# BPPower_Management.net
KiCad netlist of a schematic drawn in Altium Designer
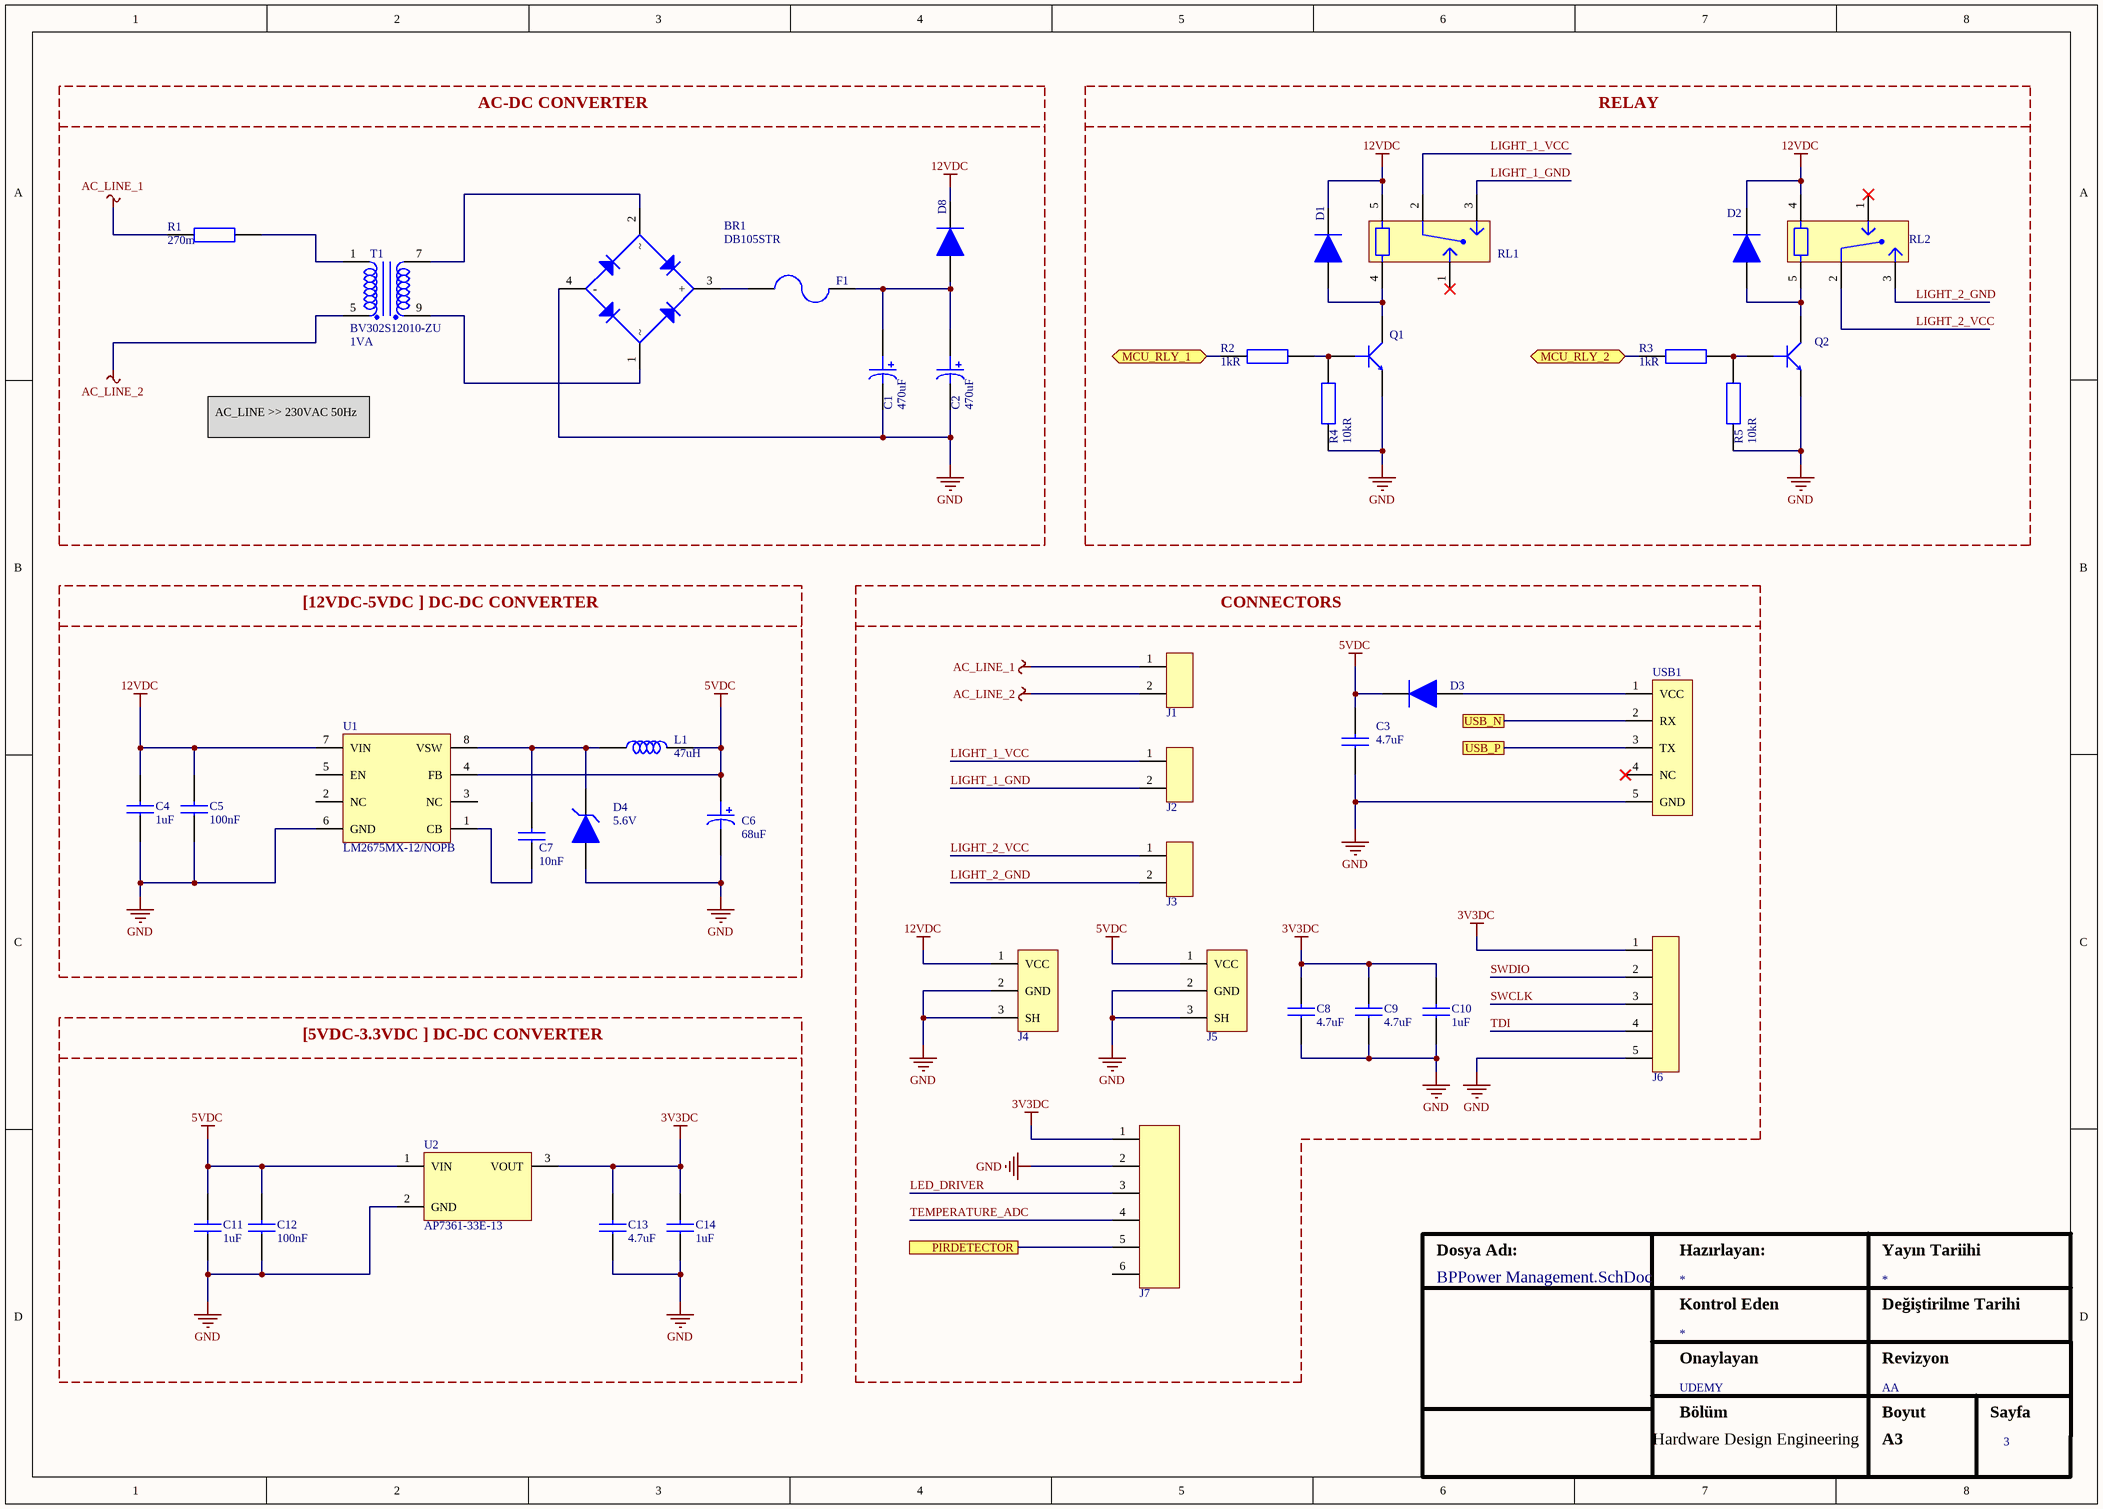
[diagram p0: BPPower Management.SchDoc]

(export (version "E")
  (design (tool "Eeschema 10.0.6"))
  (components
    (comp (ref "BR1")
      (value "DB105STR")
      (footprint "DB105STR")
      (description "Bridge Diode AC-DC")
      (fields (field (name "MANUFACTURER") "Sangdest Microelectronics") (field (name "DESIGNED BY") "BERK"))
      (libsource (lib "UDEMY_Library") (part "DB105STR"))
    )
    (comp (ref "C1")
      (value "ESH477M050AH4AA")
      (footprint "CAP_RADIAL_D10_P5")
      (description "CAP ALU ELEC 470uF 50V RADIAL")
      (fields
        (field (name "MANUFACTURER") "KEMET")
        (field (name "TOLERANCE") "20%")
        (field (name "CAPACITANCE") "470uF")
        (field (name "DESIGNED BY") "BERK")
      )
      (libsource (lib "UDEMY_Library") (part "CAP ALU ELEC 470uF 50V"))
    )
    (comp (ref "C2")
      (value "ESH477M050AH4AA")
      (footprint "CAP_RADIAL_D10_P5")
      (description "CAP ALU ELEC 470uF 50V RADIAL")
      (fields
        (field (name "MANUFACTURER") "KEMET")
        (field (name "TOLERANCE") "20%")
        (field (name "CAPACITANCE") "470uF")
        (field (name "DESIGNED BY") "BERK")
      )
      (libsource (lib "UDEMY_Library") (part "CAP ALU ELEC 470uF 50V"))
    )
    (comp (ref "C3")
      (value "CL21A475KAQNNNE")
      (footprint "CAP_0805")
      (description "CAP CER 4.7uF %10 0805")
      (fields
        (field (name "MANUFACTURER") "Samsung")
        (field (name "TOLERANCE") "10%")
        (field (name "CAPACITANCE") "4.7uF")
        (field (name "DESIGNED BY") "BERK")
      )
      (libsource (lib "UDEMY_Library") (part "CAP CER 4.7uF 0805"))
    )
    (comp (ref "C4")
      (value "CL21B105KBFNNNE")
      (footprint "CAP_0805")
      (description "CAP CER 1uF %10 0805")
      (fields
        (field (name "MANUFACTURER") "Samsung")
        (field (name "TOLERANCE") "10%")
        (field (name "CAPACITANCE") "1uF")
        (field (name "DESIGNED BY") "BERK")
      )
      (libsource (lib "UDEMY_Library") (part "CAP CER 1uF 0805"))
    )
    (comp (ref "C5")
      (value "CL21B104KBCNNNC")
      (footprint "CAP_0805")
      (description "CAP CER 100nF %10 0805")
      (fields
        (field (name "MANUFACTURER") "Samsung")
        (field (name "TOLERANCE") "10%")
        (field (name "CAPACITANCE") "100nF")
        (field (name "DESIGNED BY") "BERK")
      )
      (libsource (lib "UDEMY_Library") (part "CAP CER 100nF 0805"))
    )
    (comp (ref "C6")
      (value "EEV686M035A9HAA")
      (footprint "CAP_EEVseries")
      (description "Cap Aluminum Lytic 68uF 35V 20% (6.3 X 7.7mm) SMD 280mA 2000h 105C T/R")
      (fields
        (field (name "MANUFACTURER") "KEMET")
        (field (name "TOLERANCE") "20%")
        (field (name "CAPACITANCE") "68uF")
      )
      (libsource (lib "UDEMY_Library") (part "CAP ALU 68uF"))
    )
    (comp (ref "C7")
      (value "0603B103K160CT")
      (footprint "CAP_0603")
      (description "CAP CER 10nF %10 0603")
      (fields
        (field (name "MANUFACTURER") "Walsin Technologies")
        (field (name "TOLERANCE") "10%")
        (field (name "CAPACITANCE") "10nF")
        (field (name "DESIGNED BY") "BERK")
      )
      (libsource (lib "UDEMY_Library") (part "CAP CER 10nF 0603"))
    )
    (comp (ref "C8")
      (value "CL21A475KAQNNNE")
      (footprint "CAP_0805")
      (description "CAP CER 4.7uF %10 0805")
      (fields
        (field (name "MANUFACTURER") "Samsung")
        (field (name "TOLERANCE") "10%")
        (field (name "CAPACITANCE") "4.7uF")
        (field (name "DESIGNED BY") "BERK")
      )
      (libsource (lib "UDEMY_Library") (part "CAP CER 4.7uF 0805"))
    )
    (comp (ref "C9")
      (value "CL21A475KAQNNNE")
      (footprint "CAP_0805")
      (description "CAP CER 4.7uF %10 0805")
      (fields
        (field (name "MANUFACTURER") "Samsung")
        (field (name "TOLERANCE") "10%")
        (field (name "CAPACITANCE") "4.7uF")
        (field (name "DESIGNED BY") "BERK")
      )
      (libsource (lib "UDEMY_Library") (part "CAP CER 4.7uF 0805"))
    )
    (comp (ref "C10")
      (value "CL21B105KBFNNNE")
      (footprint "CAP_0805")
      (description "CAP CER 1uF %10 0805")
      (fields
        (field (name "MANUFACTURER") "Samsung")
        (field (name "TOLERANCE") "10%")
        (field (name "CAPACITANCE") "1uF")
        (field (name "DESIGNED BY") "BERK")
      )
      (libsource (lib "UDEMY_Library") (part "CAP CER 1uF 0805"))
    )
    (comp (ref "C11")
      (value "CL21B105KBFNNNE")
      (footprint "CAP_0805")
      (description "CAP CER 1uF %10 0805")
      (fields
        (field (name "MANUFACTURER") "Samsung")
        (field (name "TOLERANCE") "10%")
        (field (name "CAPACITANCE") "1uF")
        (field (name "DESIGNED BY") "BERK")
      )
      (libsource (lib "UDEMY_Library") (part "CAP CER 1uF 0805"))
    )
    (comp (ref "C12")
      (value "C0603C104K5RACTU")
      (footprint "CAP_0603")
      (description "CAP CER 100nF %10 0603 SMD")
      (fields
        (field (name "MANUFACTURER") "KEMET")
        (field (name "TOLERANCE") "10%")
        (field (name "CAPACITANCE") "100nF")
        (field (name "DESIGNED BY") "BERK")
      )
      (libsource (lib "UDEMY_Library") (part "CAP CER 100nF 0603"))
    )
    (comp (ref "C13")
      (value "CL21A475KAQNNNE")
      (footprint "CAP_0805")
      (description "CAP CER 4.7uF %10 0805")
      (fields
        (field (name "MANUFACTURER") "Samsung")
        (field (name "TOLERANCE") "10%")
        (field (name "CAPACITANCE") "4.7uF")
        (field (name "DESIGNED BY") "BERK")
      )
      (libsource (lib "UDEMY_Library") (part "CAP CER 4.7uF 0805"))
    )
    (comp (ref "C14")
      (value "CL21B105KBFNNNE")
      (footprint "CAP_0805")
      (description "CAP CER 1uF %10 0805")
      (fields
        (field (name "MANUFACTURER") "Samsung")
        (field (name "TOLERANCE") "10%")
        (field (name "CAPACITANCE") "1uF")
        (field (name "DESIGNED BY") "BERK")
      )
      (libsource (lib "UDEMY_Library") (part "CAP CER 1uF 0805"))
    )
    (comp (ref "D1")
      (value "1N4148WS")
      (footprint "SOD323F")
      (description "Diode, Single, 75 V, 150 mA, 1 V, 4 ns")
      (fields
        (field (name "MANUFACTURER") "ON Semiconductor / Fairchild")
        (field (name "DESIGNED BY") "BERK")
      )
      (libsource (lib "UDEMY_Library") (part "1N4148WS"))
    )
    (comp (ref "D2")
      (value "1N4148WS")
      (footprint "SOD323F")
      (description "Diode, Single, 75 V, 150 mA, 1 V, 4 ns")
      (fields
        (field (name "MANUFACTURER") "ON Semiconductor / Fairchild")
        (field (name "DESIGNED BY") "BERK")
      )
      (libsource (lib "UDEMY_Library") (part "1N4148WS"))
    )
    (comp (ref "D3")
      (value "1N4148WS")
      (footprint "SOD323F")
      (description "Diode, Single, 75 V, 150 mA, 1 V, 4 ns")
      (fields
        (field (name "MANUFACTURER") "ON Semiconductor / Fairchild")
        (field (name "DESIGNED BY") "BERK")
      )
      (libsource (lib "UDEMY_Library") (part "1N4148WS"))
    )
    (comp (ref "D4")
      (value "1SMB5919BT3G")
      (footprint "SMB")
      (description "Diode Zener Single 5.6V 5% 3W 2-Pin SMB T/R")
      (fields
        (field (name "MANUFACTURER") "ON Semiconductor")
        (field (name "TOLERANCE") "5%")
        (field (name "WORKING VOLTAGE") "5.6V")
        (field (name "DESIGNED BY") "BERK")
      )
      (libsource (lib "UDEMY_Library") (part "1SMB5919BT3G"))
    )
    (comp (ref "D8")
      (value "1N4148WS")
      (footprint "SOD323F")
      (description "Diode, Single, 75 V, 150 mA, 1 V, 4 ns")
      (fields
        (field (name "MANUFACTURER") "ON Semiconductor / Fairchild")
        (field (name "DESIGNED BY") "BERK")
      )
      (libsource (lib "UDEMY_Library") (part "1N4148WS"))
    )
    (comp (ref "F1")
      (value "3413.0216.22")
      (footprint "BPSchematic:3413.0216.22")
      (description "FUSE BRD MNT 1A 32VAC 63VDC 1206")
      (fields (field (name "MANUFACTURER") "Schurter") (field (name "DESIGNED BY") "BERK"))
      (libsource (lib "UDEMY_Library") (part "FUSE 3413.0216.22"))
    )
    (comp (ref "J1")
      (value "TBP01R1-508-02BE")
      (footprint "BPSchematic:TBP01R1-508")
      (description "Conn Shrouded Header HDR 2 POS 5.08mm Solder RA Side Entry Thru-Hole Bag")
      (fields (field (name "MANUFACTURER") "CUI") (field (name "DESIGNED BY") "BERK"))
      (libsource (lib "UDEMY_Library") (part "TBP01R1-508-02BE"))
    )
    (comp (ref "J2")
      (value "TBP01R1-508-02BE")
      (footprint "BPSchematic:TBP01R1-508")
      (description "Conn Shrouded Header HDR 2 POS 5.08mm Solder RA Side Entry Thru-Hole Bag")
      (fields (field (name "MANUFACTURER") "CUI") (field (name "DESIGNED BY") "BERK"))
      (libsource (lib "UDEMY_Library") (part "TBP01R1-508-02BE"))
    )
    (comp (ref "J3")
      (value "TBP01R1-508-02BE")
      (footprint "BPSchematic:TBP01R1-508")
      (description "Conn Shrouded Header HDR 2 POS 5.08mm Solder RA Side Entry Thru-Hole Bag")
      (fields (field (name "MANUFACTURER") "CUI") (field (name "DESIGNED BY") "BERK"))
      (libsource (lib "UDEMY_Library") (part "TBP01R1-508-02BE"))
    )
    (comp (ref "J4")
      (value "PJ-037AH-SMT-TR")
      (footprint "JACK")
      (description "DC Power Connectors Power Jacks")
      (fields (field (name "MANUFACTURER") "CUI") (field (name "DESIGNED BY") "BERK"))
      (libsource (lib "UDEMY_Library") (part "PJ-037AH-SMT-TR"))
    )
    (comp (ref "J5")
      (value "PJ-037AH-SMT-TR")
      (footprint "JACK")
      (description "DC Power Connectors Power Jacks")
      (fields (field (name "MANUFACTURER") "CUI") (field (name "DESIGNED BY") "BERK"))
      (libsource (lib "UDEMY_Library") (part "PJ-037AH-SMT-TR"))
    )
    (comp (ref "J6")
      (value "SMH-105-02-L-S")
      (footprint "PINHEADER1X5_RA")
      (description ".100 C.L. HORIZONTAL SMT SOCKET")
      (fields (field (name "MANUFACTURER") "Samtec") (field (name "DESIGNED BY") "BERK"))
      (libsource (lib "UDEMY_Library") (part "SMH-105-02-L-S"))
    )
    (comp (ref "J7")
      (value "64800611622")
      (footprint "BPSchematic:64800611622")
      (description "1.50mm 6PIN Connector")
      (fields (field (name "MANUFACTURER") "Wurth Electronics"))
      (libsource (lib "UDEMY_Library") (part "64800611622_conn_6pin"))
    )
    (comp (ref "L1")
      (value "78438335470")
      (footprint "IND_1212")
      (description "FIXED IND 47UH 390MA 2.3 OHM SMD")
      (fields
        (field (name "MANUFACTURER") "Wurth Electronics")
        (field (name "TOLERANCE") "30%")
        (field (name "INDUCTANCE") "47uH")
        (field (name "DESIGNED BY") "BERK")
      )
      (libsource (lib "UDEMY_Library") (part "IND 47uH"))
    )
    (comp (ref "Q1")
      (value "MMBT3904-7-F")
      (footprint "SOT-23F")
      (description "Transistor General Purpose BJT NPN 40 Volt 0.2A Automotive 3-Pin SOT-23")
      (fields (field (name "MANUFACTURER") "Diodes Zetex") (field (name "DESIGNED BY") "BERK"))
      (libsource (lib "UDEMY_Library") (part "MMBT3904-7-F"))
    )
    (comp (ref "Q2")
      (value "MMBT3904-7-F")
      (footprint "SOT-23F")
      (description "Transistor General Purpose BJT NPN 40 Volt 0.2A Automotive 3-Pin SOT-23")
      (fields (field (name "MANUFACTURER") "Diodes Zetex") (field (name "DESIGNED BY") "BERK"))
      (libsource (lib "UDEMY_Library") (part "MMBT3904-7-F"))
    )
    (comp (ref "R1")
      (value "5WD27")
      (footprint "RES_AXIAL_W")
      (description "Resistor 5 Watt Cermet Wirewound Flameproof .27 Ohm 5% Axial Lead")
      (fields
        (field (name "MANUFACTURER") "NTE Electronics")
        (field (name "TOLERANCE") "5%")
        (field (name "RESISTANCE") "270m")
        (field (name "DESIGNED BY") "BERK")
      )
      (libsource (lib "UDEMY_Library") (part "5WD27"))
    )
    (comp (ref "R2")
      (value "RC0603FR-0710KL")
      (footprint "RES_0603")
      (description "RES 1K %1 OHM 0603 SMD")
      (fields
        (field (name "MANUFACTURER") "Yageo")
        (field (name "MANUFACTURER PART NUMBER") "RC0603JR-071KL")
        (field (name "RESISTANCE") "1kR")
        (field (name "DESIGNED BY") "BERK")
      )
      (libsource (lib "UDEMY_Library") (part "RES 1K OHM 0603"))
    )
    (comp (ref "R3")
      (value "RC0603FR-0710KL")
      (footprint "RES_0603")
      (description "RES 1K %1 OHM 0603 SMD")
      (fields
        (field (name "MANUFACTURER") "Yageo")
        (field (name "MANUFACTURER PART NUMBER") "RC0603JR-071KL")
        (field (name "RESISTANCE") "1kR")
        (field (name "DESIGNED BY") "BERK")
      )
      (libsource (lib "UDEMY_Library") (part "RES 1K OHM 0603"))
    )
    (comp (ref "R4")
      (value "RC0603FR-0710KL")
      (footprint "RES_0603")
      (description "RES 10K %1 OHM 0603 SMD")
      (fields
        (field (name "MANUFACTURER") "Yageo")
        (field (name "TOLERANCE") "1%")
        (field (name "RESISTANCE") "10kR")
        (field (name "DESIGNED BY") "BERK")
      )
      (libsource (lib "UDEMY_Library") (part "RES 10K OHM 0603"))
    )
    (comp (ref "R5")
      (value "RC0603FR-0710KL")
      (footprint "RES_0603")
      (description "RES 10K %1 OHM 0603 SMD")
      (fields
        (field (name "MANUFACTURER") "Yageo")
        (field (name "TOLERANCE") "1%")
        (field (name "RESISTANCE") "10kR")
        (field (name "DESIGNED BY") "BERK")
      )
      (libsource (lib "UDEMY_Library") (part "RES 10K OHM 0603"))
    )
    (comp (ref "RL1")
      (value "ALQ112")
      (footprint "ALQ112")
      (description "General Purpose Relay SPDT (1 Form C) 12VDC Coil Through Hole")
      (fields (field (name "MANUFACTURER") "Panasonic") (field (name "DESIGNED BY") "BERK"))
      (libsource (lib "") (part "ALQ112_1"))
    )
    (comp (ref "RL2")
      (value "ALQ112")
      (footprint "ALQ112")
      (description "General Purpose Relay SPDT (1 Form C) 12VDC Coil Through Hole")
      (fields (field (name "MANUFACTURER") "Panasonic") (field (name "DESIGNED BY") "BERK"))
      (libsource (lib "UDEMY_Library") (part "ALQ112"))
    )
    (comp (ref "T1")
      (value "BV302S12010-ZU")
      (footprint "BV302S")
      (description "230-12 Transformer 1VA")
      (fields
        (field (name "MANUFACTURER") "Zettler Magnetics")
        (field (name "RATED POWER") "1VA")
        (field (name "DESIGNED BY") "BERK")
      )
      (libsource (lib "UDEMY_Library") (part "BV302S12010-ZU"))
    )
    (comp (ref "U1")
      (value "LM2675MX-12/NOPB")
      (footprint "SOIC8")
      (description "Switching Voltage Regulators Pwr Cnvtr Hi Eff 1A SD Vtg Reg")
      (fields (field (name "MANUFACTURER") "TI National Semiconductor") (field (name "DESIGNED BY") "BERK"))
      (libsource (lib "UDEMY_Library") (part "LM2675MX-12/NOPB"))
    )
    (comp (ref "U2")
      (value "AP7361-33E-13")
      (footprint "SOT223")
      (description "LDO Regulator Pos 3.3V 1A 4-Pin(3+Tab) SOT-223 T/R")
      (fields (field (name "MANUFACTURER") "Diodes") (field (name "DESIGNED BY") "BERK"))
      (libsource (lib "UDEMY_Library") (part "AP7361-33E-13"))
    )
    (comp (ref "USB1")
      (value "10118192-0001LF")
      (footprint "MICRO_B_USB")
      (description "CONN RCPT USB2.0 MICRO B SMD R/A")
      (fields (field (name "MANUFACTURER") "Amphenol FCI") (field (name "DESIGNED BY") "BERK"))
      (libsource (lib "UDEMY_Library") (part "Micro B USB Connector"))
    )
  )
  (nets
    (net (code "1") (name "/LED_DRIVER") (class "Default") (node (ref "J7") (pin "3") (pintype "power_in")))
    (net (code "2") (name "/LIGHT_1_GND") (class "Default")
      (node (ref "J2") (pin "2") (pinfunction "2_2") (pintype "power_in"))
      (node (ref "RL1") (pin "3") (pinfunction "3_3") (pintype "passive"))
    )
    (net (code "3") (name "/LIGHT_1_VCC") (class "Default")
      (node (ref "J2") (pin "1") (pinfunction "1_1") (pintype "power_in"))
      (node (ref "RL1") (pin "2") (pinfunction "2_2") (pintype "passive"))
    )
    (net (code "4") (name "/LIGHT_2_GND") (class "Default")
      (node (ref "J3") (pin "2") (pinfunction "2_2") (pintype "power_in"))
      (node (ref "RL2") (pin "3") (pinfunction "3_3") (pintype "passive"))
    )
    (net (code "5") (name "/LIGHT_2_VCC") (class "Default")
      (node (ref "J3") (pin "1") (pinfunction "1_1") (pintype "power_in"))
      (node (ref "RL2") (pin "2") (pinfunction "2_2") (pintype "passive"))
    )
    (net (code "6") (name "/MCU_RLY_1") (class "Default")
      (node (ref "R2") (pin "1") (pinfunction "1_1") (pintype "passive"))
    )
    (net (code "7") (name "/MCU_RLY_2") (class "Default")
      (node (ref "R3") (pin "1") (pinfunction "1_1") (pintype "passive"))
    )
    (net (code "8") (name "/PIRDETECTOR") (class "Default") (node (ref "J7") (pin "5") (pintype "power_in")))
    (net (code "9") (name "/SWCLK") (class "Default")
      (node (ref "J6") (pin "3") (pinfunction "3_3") (pintype "power_in"))
    )
    (net (code "10") (name "/SWDIO") (class "Default")
      (node (ref "J6") (pin "2") (pinfunction "2_2") (pintype "power_in"))
    )
    (net (code "11") (name "/TDI") (class "Default")
      (node (ref "J6") (pin "4") (pinfunction "4_4") (pintype "power_in"))
    )
    (net (code "12") (name "/TEMPERATURE_ADC") (class "Default")
      (node (ref "J7") (pin "4") (pintype "power_in"))
    )
    (net (code "13") (name "/USB_N") (class "Default")
      (node (ref "USB1") (pin "2") (pinfunction "RX_2") (pintype "power_in"))
    )
    (net (code "14") (name "/USB_P") (class "Default")
      (node (ref "USB1") (pin "3") (pinfunction "TX_3") (pintype "power_in"))
    )
    (net (code "15") (name "3V3DC") (class "Default")
      (node (ref "C10") (pin "2") (pinfunction "2_2") (pintype "passive"))
      (node (ref "C13") (pin "2") (pinfunction "2_2") (pintype "passive"))
      (node (ref "C14") (pin "2") (pinfunction "2_2") (pintype "passive"))
      (node (ref "C8") (pin "2") (pinfunction "2_2") (pintype "passive"))
      (node (ref "C9") (pin "2") (pinfunction "2_2") (pintype "passive"))
      (node (ref "J6") (pin "1") (pinfunction "1_1") (pintype "power_in"))
      (node (ref "J7") (pin "1") (pintype "power_in"))
      (node (ref "U2") (pin "3") (pinfunction "VOUT_3") (pintype "passive"))
    )
    (net (code "16") (name "5VDC") (class "Default")
      (node (ref "C11") (pin "2") (pinfunction "2_2") (pintype "passive"))
      (node (ref "C12") (pin "2") (pinfunction "2_2") (pintype "passive"))
      (node (ref "C3") (pin "2") (pinfunction "2_2") (pintype "passive"))
      (node (ref "C6") (pin "1") (pinfunction "1_1") (pintype "passive"))
      (node (ref "D3") (pin "1") (pinfunction "1_1") (pintype "power_in"))
      (node (ref "J5") (pin "1") (pinfunction "VCC_1") (pintype "power_in"))
      (node (ref "L1") (pin "2") (pinfunction "2_2") (pintype "passive"))
      (node (ref "U1") (pin "4") (pinfunction "FB_4") (pintype "passive"))
      (node (ref "U2") (pin "1") (pinfunction "VIN_1") (pintype "passive"))
    )
    (net (code "17") (name "12VDC") (class "Default")
      (node (ref "C4") (pin "2") (pinfunction "2_2") (pintype "passive"))
      (node (ref "C5") (pin "2") (pinfunction "2_2") (pintype "passive"))
      (node (ref "D1") (pin "1") (pinfunction "1_1") (pintype "power_in"))
      (node (ref "D2") (pin "1") (pinfunction "1_1") (pintype "power_in"))
      (node (ref "D8") (pin "1") (pinfunction "1_1") (pintype "power_in"))
      (node (ref "J4") (pin "1") (pinfunction "VCC_1") (pintype "power_in"))
      (node (ref "RL1") (pin "5") (pinfunction "5_5") (pintype "passive"))
      (node (ref "RL2") (pin "4") (pinfunction "4_4") (pintype "passive"))
      (node (ref "U1") (pin "7") (pinfunction "VIN_7") (pintype "passive"))
    )
    (net (code "18") (name "AC_LINE_1") (class "Default")
      (node (ref "J1") (pin "1") (pinfunction "1_1") (pintype "power_in"))
      (node (ref "R1") (pin "1") (pinfunction "1_1") (pintype "passive"))
    )
    (net (code "19") (name "AC_LINE_2") (class "Default")
      (node (ref "J1") (pin "2") (pinfunction "2_2") (pintype "power_in"))
      (node (ref "T1") (pin "5") (pinfunction "5_5") (pintype "passive"))
    )
    (net (code "20") (name "GND") (class "Default")
      (node (ref "BR1") (pin "4") (pinfunction "-_4") (pintype "passive"))
      (node (ref "C1") (pin "2") (pinfunction "2_2") (pintype "passive"))
      (node (ref "C10") (pin "1") (pinfunction "1_1") (pintype "passive"))
      (node (ref "C11") (pin "1") (pinfunction "1_1") (pintype "passive"))
      (node (ref "C12") (pin "1") (pinfunction "1_1") (pintype "passive"))
      (node (ref "C13") (pin "1") (pinfunction "1_1") (pintype "passive"))
      (node (ref "C14") (pin "1") (pinfunction "1_1") (pintype "passive"))
      (node (ref "C2") (pin "2") (pinfunction "2_2") (pintype "passive"))
      (node (ref "C3") (pin "1") (pinfunction "1_1") (pintype "passive"))
      (node (ref "C4") (pin "1") (pinfunction "1_1") (pintype "passive"))
      (node (ref "C5") (pin "1") (pinfunction "1_1") (pintype "passive"))
      (node (ref "C6") (pin "2") (pinfunction "2_2") (pintype "passive"))
      (node (ref "C8") (pin "1") (pinfunction "1_1") (pintype "passive"))
      (node (ref "C9") (pin "1") (pinfunction "1_1") (pintype "passive"))
      (node (ref "D4") (pin "A") (pinfunction "A_A") (pintype "passive"))
      (node (ref "J4") (pin "2") (pinfunction "GND_2") (pintype "power_in"))
      (node (ref "J4") (pin "3") (pinfunction "SH_3") (pintype "power_in"))
      (node (ref "J5") (pin "2") (pinfunction "GND_2") (pintype "power_in"))
      (node (ref "J5") (pin "3") (pinfunction "SH_3") (pintype "power_in"))
      (node (ref "J6") (pin "5") (pinfunction "5_5") (pintype "power_in"))
      (node (ref "J7") (pin "2") (pintype "power_in"))
      (node (ref "Q1") (pin "2") (pinfunction "E_2") (pintype "power_in"))
      (node (ref "Q2") (pin "2") (pinfunction "E_2") (pintype "power_in"))
      (node (ref "R4") (pin "1") (pinfunction "1_1") (pintype "passive"))
      (node (ref "R5") (pin "1") (pinfunction "1_1") (pintype "passive"))
      (node (ref "U1") (pin "6") (pinfunction "GND_6") (pintype "passive"))
      (node (ref "U2") (pin "2") (pinfunction "GND_2") (pintype "passive"))
      (node (ref "USB1") (pin "5") (pinfunction "GND_5") (pintype "power_in"))
    )
    (net (code "21") (name "Net-(BR1-+)") (class "Default")
      (node (ref "BR1") (pin "3") (pinfunction "+_3") (pintype "passive"))
      (node (ref "F1") (pin "1") (pinfunction "1_1") (pintype "passive"))
    )
    (net (code "22") (name "Net-(BR1-~-Pad1)") (class "Default")
      (node (ref "BR1") (pin "1") (pinfunction "~_1") (pintype "passive"))
      (node (ref "T1") (pin "9") (pinfunction "9_9") (pintype "passive"))
    )
    (net (code "23") (name "Net-(BR1-~-Pad2)") (class "Default")
      (node (ref "BR1") (pin "2") (pinfunction "~_2") (pintype "passive"))
      (node (ref "T1") (pin "7") (pinfunction "7_7") (pintype "passive"))
    )
    (net (code "24") (name "Net-(C1-Pad1)") (class "Default")
      (node (ref "C1") (pin "1") (pinfunction "1_1") (pintype "passive"))
      (node (ref "C2") (pin "1") (pinfunction "1_1") (pintype "passive"))
      (node (ref "D8") (pin "2") (pinfunction "2_2") (pintype "power_in"))
      (node (ref "F1") (pin "2") (pinfunction "2_2") (pintype "passive"))
    )
    (net (code "25") (name "Net-(Q1-B)") (class "Default")
      (node (ref "Q1") (pin "1") (pinfunction "B_1") (pintype "power_in"))
      (node (ref "R2") (pin "2") (pinfunction "2_2") (pintype "passive"))
      (node (ref "R4") (pin "2") (pinfunction "2_2") (pintype "passive"))
    )
    (net (code "26") (name "Net-(Q1-C)") (class "Default")
      (node (ref "D1") (pin "2") (pinfunction "2_2") (pintype "power_in"))
      (node (ref "Q1") (pin "3") (pinfunction "C_3") (pintype "power_in"))
      (node (ref "RL1") (pin "4") (pinfunction "4_4") (pintype "passive"))
    )
    (net (code "27") (name "Net-(Q2-B)") (class "Default")
      (node (ref "Q2") (pin "1") (pinfunction "B_1") (pintype "power_in"))
      (node (ref "R3") (pin "2") (pinfunction "2_2") (pintype "passive"))
      (node (ref "R5") (pin "2") (pinfunction "2_2") (pintype "passive"))
    )
    (net (code "28") (name "Net-(Q2-C)") (class "Default")
      (node (ref "D2") (pin "2") (pinfunction "2_2") (pintype "power_in"))
      (node (ref "Q2") (pin "3") (pinfunction "C_3") (pintype "power_in"))
      (node (ref "RL2") (pin "5") (pinfunction "5_5") (pintype "passive"))
    )
    (net (code "29") (name "Net-(R1-Pad2)") (class "Default")
      (node (ref "R1") (pin "2") (pinfunction "2_2") (pintype "passive"))
      (node (ref "T1") (pin "1") (pinfunction "1_1") (pintype "passive"))
    )
    (net (code "30") (name "Net-(U1-CB)") (class "Default")
      (node (ref "C7") (pin "1") (pinfunction "1_1") (pintype "passive"))
      (node (ref "U1") (pin "1") (pinfunction "CB_1") (pintype "passive"))
    )
    (net (code "31") (name "Net-(U1-VSW)") (class "Default")
      (node (ref "C7") (pin "2") (pinfunction "2_2") (pintype "passive"))
      (node (ref "D4") (pin "C") (pinfunction "C_C") (pintype "passive"))
      (node (ref "L1") (pin "1") (pinfunction "1_1") (pintype "passive"))
      (node (ref "U1") (pin "8") (pinfunction "VSW_8") (pintype "passive"))
    )
    (net (code "32") (name "Net-(USB1-VCC)") (class "Default")
      (node (ref "D3") (pin "2") (pinfunction "2_2") (pintype "power_in"))
      (node (ref "USB1") (pin "1") (pinfunction "VCC_1") (pintype "power_in"))
    )
    (net (code "33") (name "unconnected-(J7-Pad6)") (class "Default")
      (node (ref "J7") (pin "6") (pintype "power_in"))
    )
    (net (code "34") (name "unconnected-(RL1-Pad1)") (class "Default")
      (node (ref "RL1") (pin "1") (pinfunction "1_1") (pintype "passive+no_connect"))
    )
    (net (code "35") (name "unconnected-(RL2-Pad1)") (class "Default")
      (node (ref "RL2") (pin "1") (pinfunction "1_1") (pintype "passive+no_connect"))
    )
    (net (code "36") (name "unconnected-(U1-EN-Pad5)") (class "Default")
      (node (ref "U1") (pin "5") (pinfunction "EN_5") (pintype "passive"))
    )
    (net (code "37") (name "unconnected-(U1-NC-Pad2)") (class "Default")
      (node (ref "U1") (pin "2") (pinfunction "NC_2") (pintype "passive"))
    )
    (net (code "38") (name "unconnected-(U1-NC-Pad3)") (class "Default")
      (node (ref "U1") (pin "3") (pinfunction "NC_3") (pintype "passive"))
    )
    (net (code "39") (name "unconnected-(USB1-NC-Pad4)") (class "Default")
      (node (ref "USB1") (pin "4") (pinfunction "NC_4") (pintype "power_in+no_connect"))
    )
  )
)
